# CircuitoPedaleiraTcc2.net
KiCad netlist of a schematic drawn in EAGLE
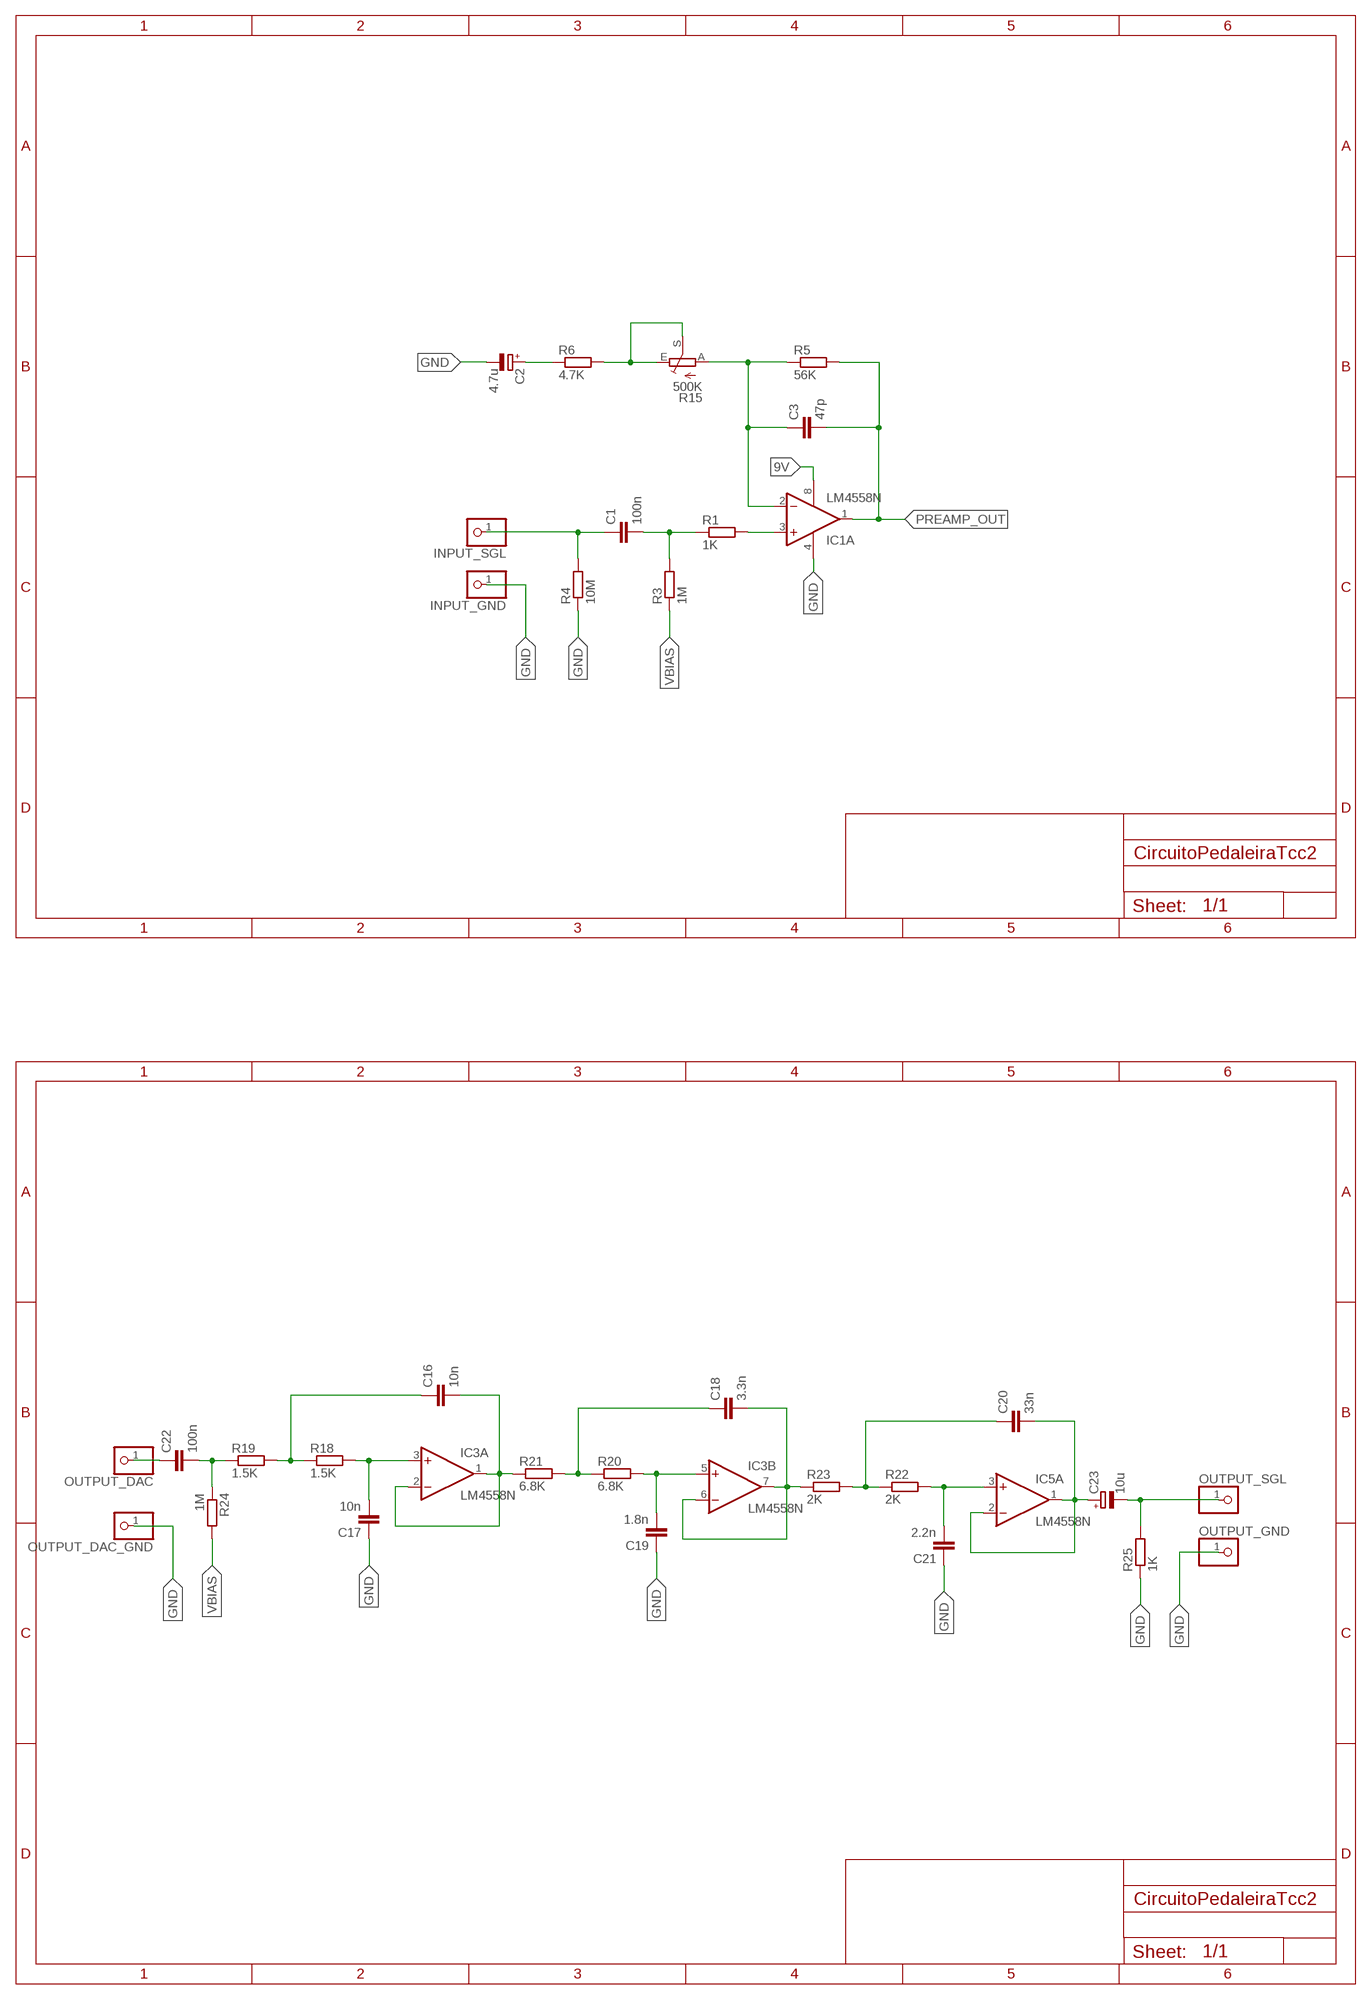
[diagram p0: schematic, sheet 1, part 1 of 3]
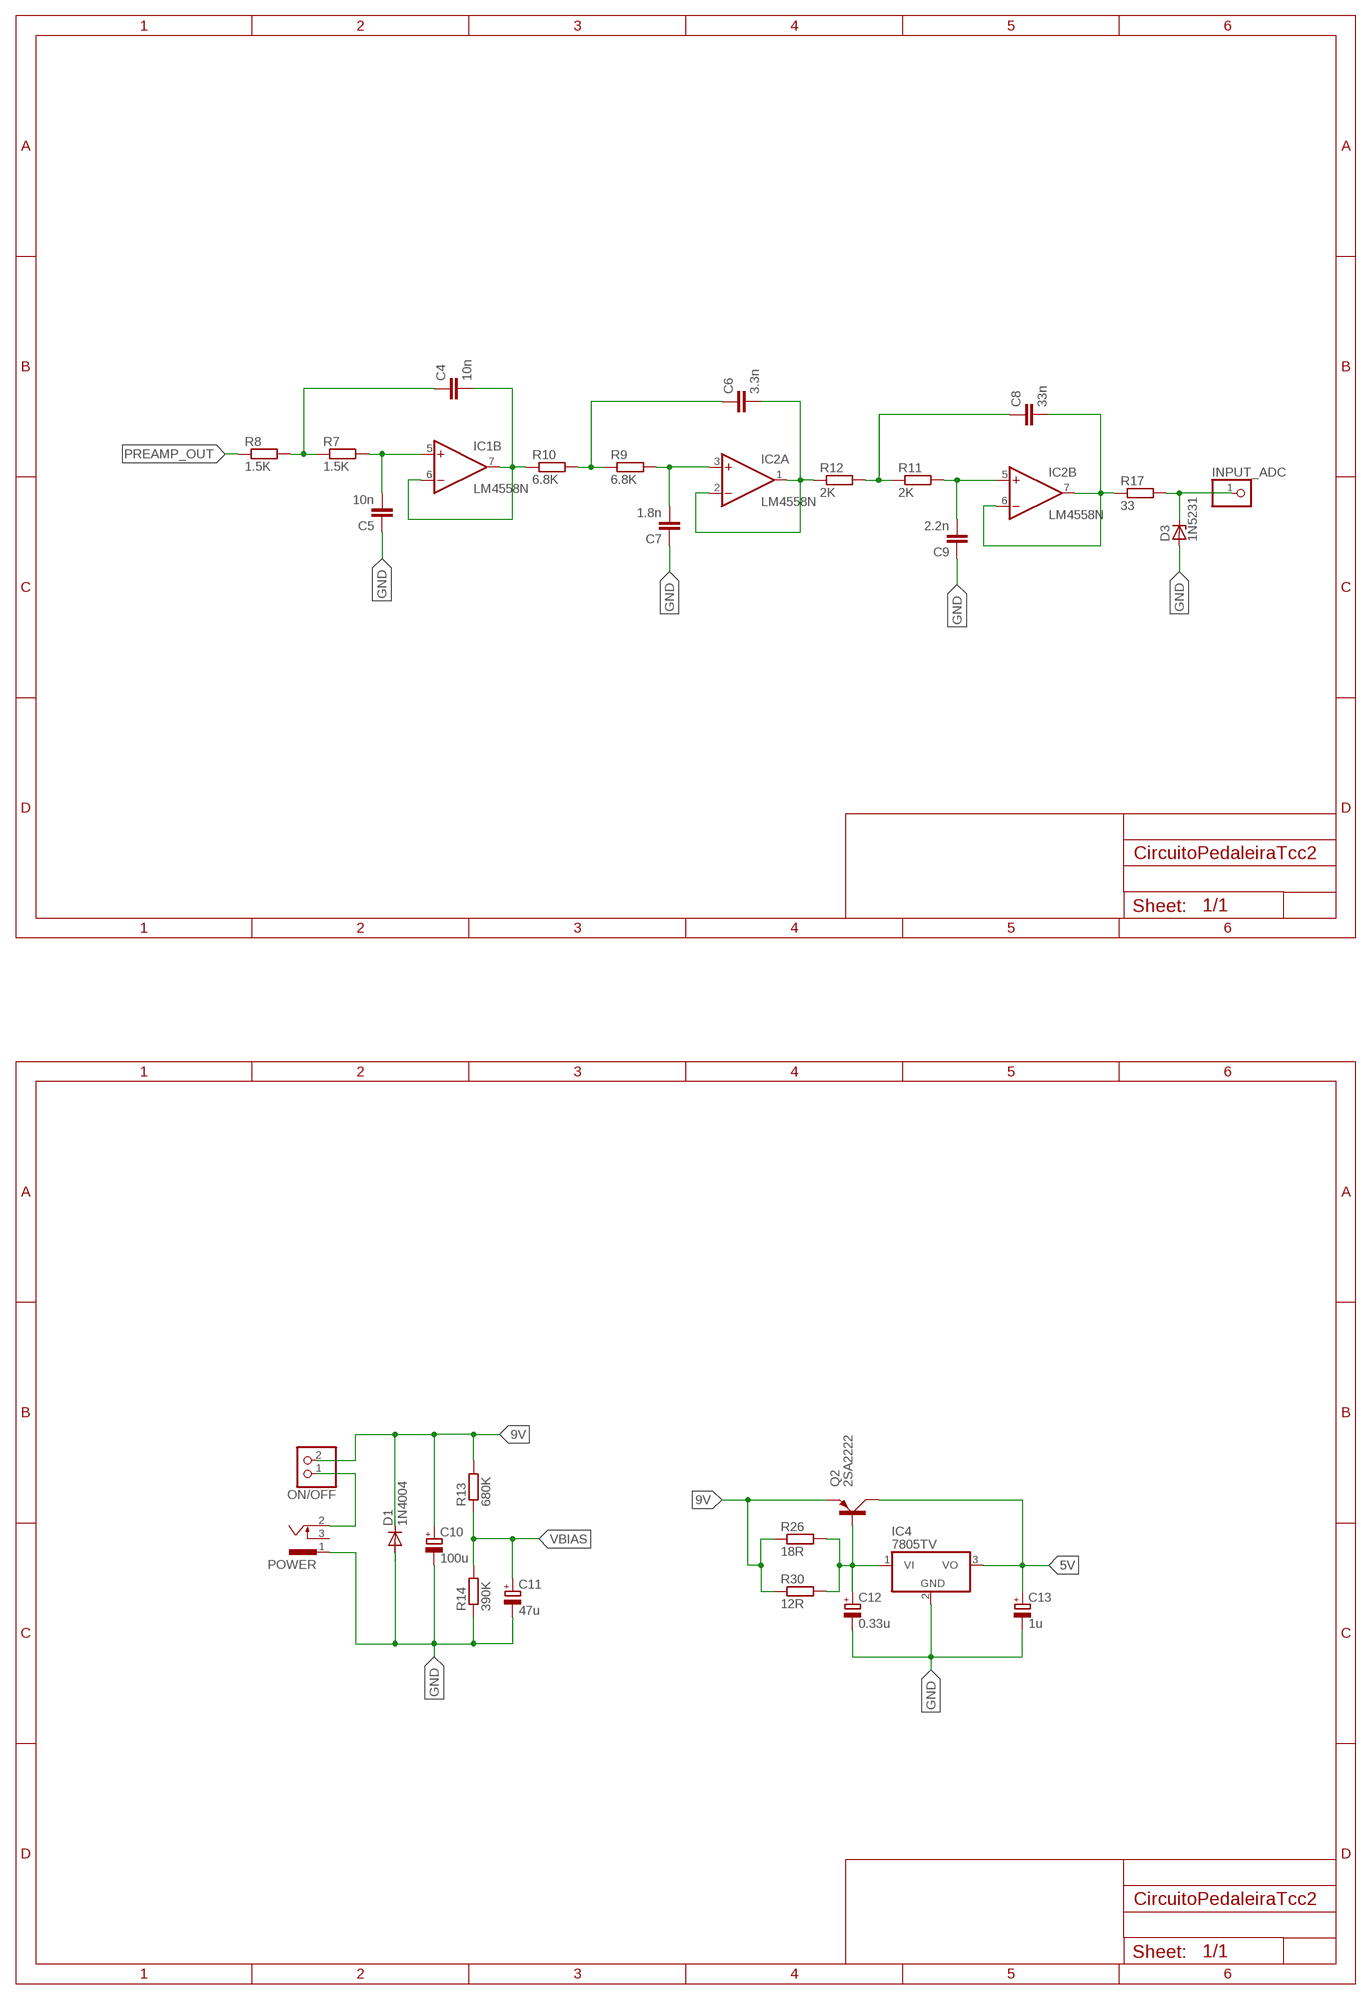
[diagram p1: schematic, sheet 1, part 2 of 3]
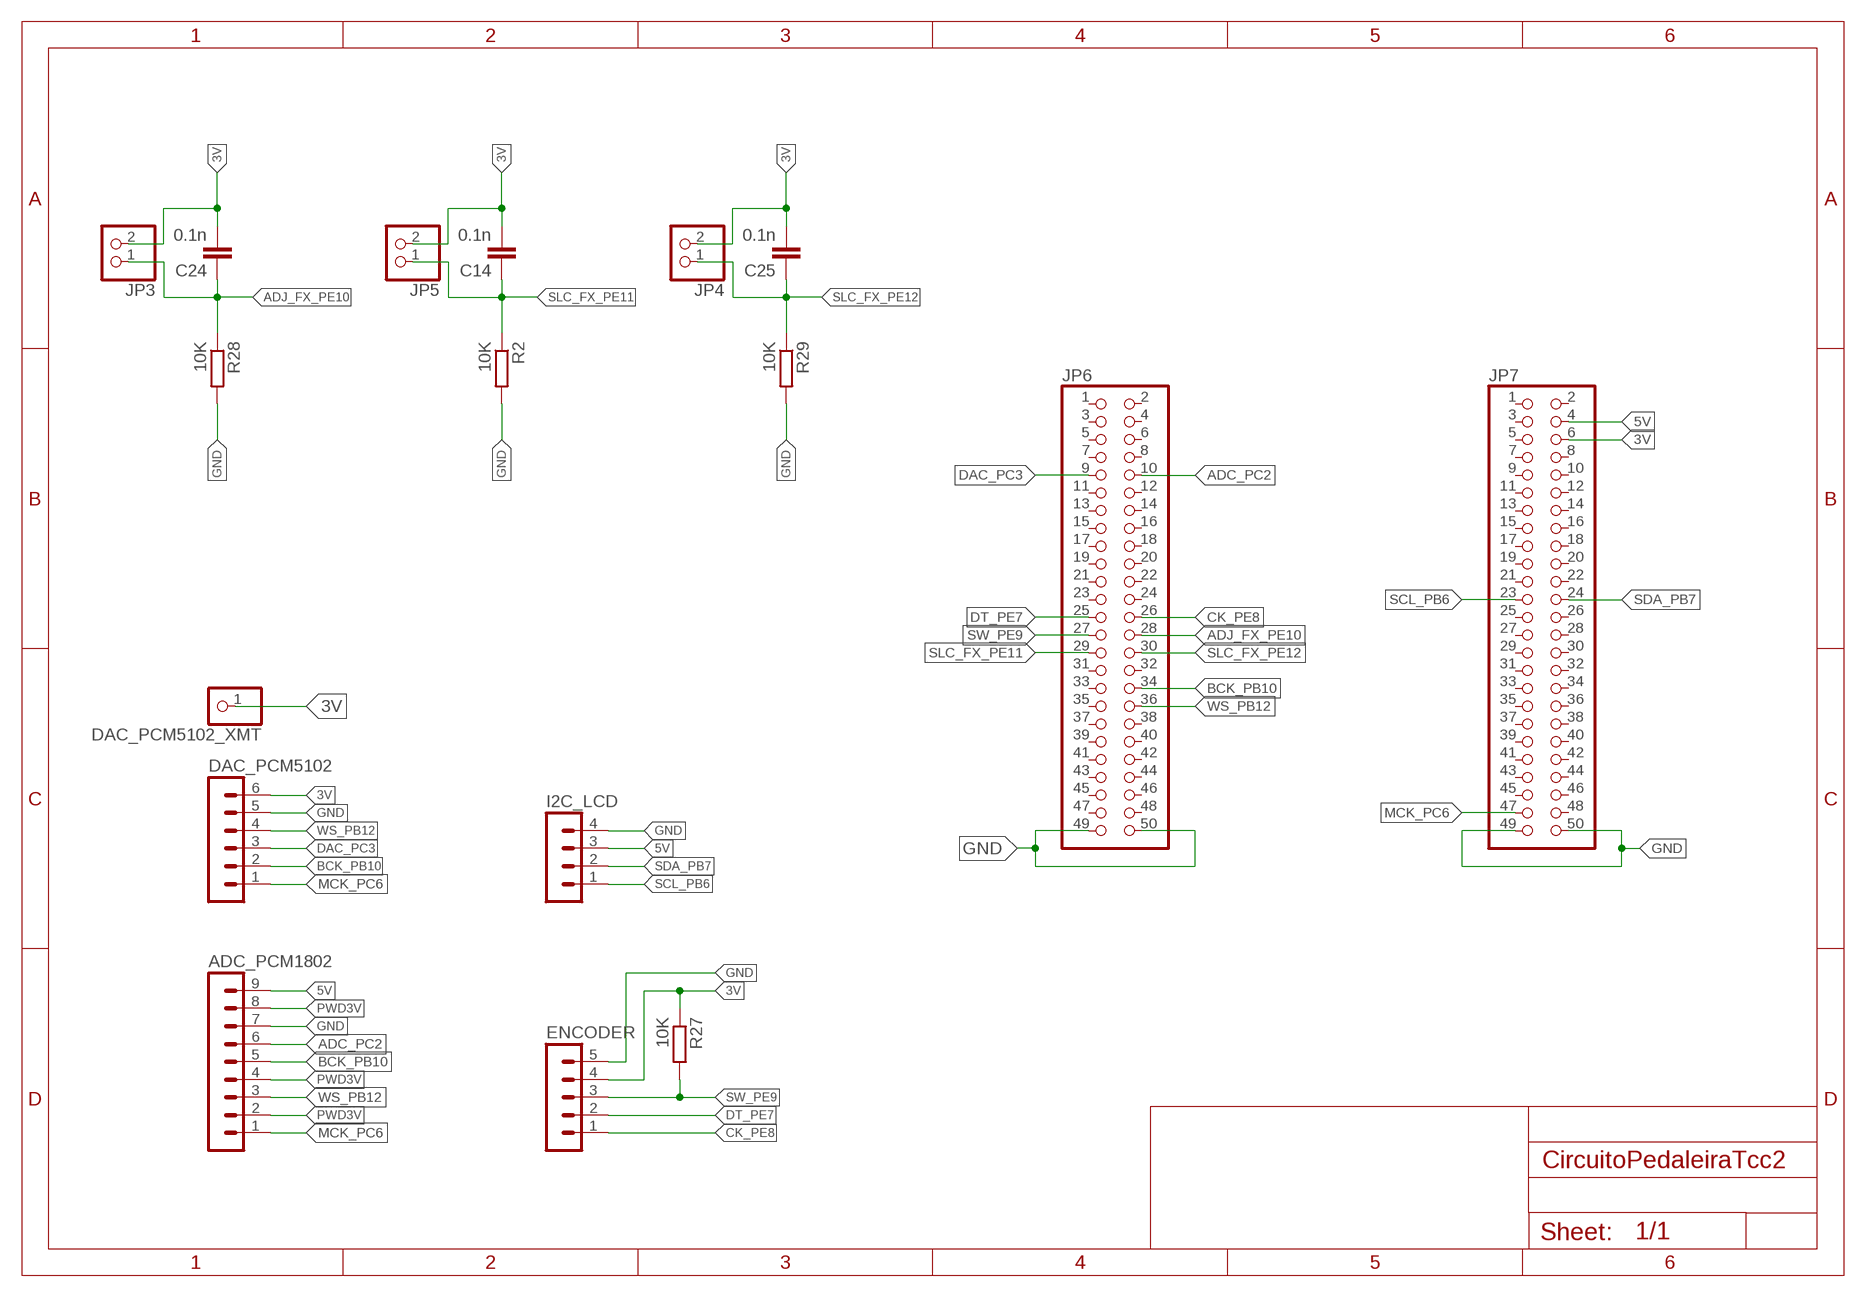
[diagram p2: schematic, sheet 1, part 3 of 3]

(export (version "E")
  (design (tool "Eeschema 10.0.6"))
  (components
    (comp (ref "ADC_PCM1802")
      (value "MA09-1")
      (footprint "eagle-import:MA09-1")
      (libsource (lib "eagle-import") (part "MA09-1"))
    )
    (comp (ref "C1")
      (value "100n")
      (footprint "eagle-import:C025-025X050")
      (libsource (lib "eagle-import") (part "C-EU025-025X050"))
    )
    (comp (ref "C2")
      (value "4.7u")
      (footprint "eagle-import:E2,5-6")
      (libsource (lib "eagle-import") (part "CPOL-EUE2.5-6"))
    )
    (comp (ref "C3")
      (value "47p")
      (footprint "eagle-import:C025-025X050")
      (libsource (lib "eagle-import") (part "C-EU025-025X050"))
    )
    (comp (ref "C4")
      (value "10n")
      (footprint "eagle-import:C025-025X050")
      (libsource (lib "eagle-import") (part "C-EU025-025X050"))
    )
    (comp (ref "C5")
      (value "10n")
      (footprint "eagle-import:C025-025X050")
      (libsource (lib "eagle-import") (part "C-EU025-025X050"))
    )
    (comp (ref "C6")
      (value "3.3n")
      (footprint "eagle-import:C025-025X050")
      (libsource (lib "eagle-import") (part "C-EU025-025X050"))
    )
    (comp (ref "C7")
      (value "1.8n")
      (footprint "eagle-import:C025-025X050")
      (libsource (lib "eagle-import") (part "C-EU025-025X050"))
    )
    (comp (ref "C8")
      (value "33n")
      (footprint "eagle-import:C025-025X050")
      (libsource (lib "eagle-import") (part "C-EU025-025X050"))
    )
    (comp (ref "C9")
      (value "2.2n")
      (footprint "eagle-import:C025-025X050")
      (libsource (lib "eagle-import") (part "C-EU025-025X050"))
    )
    (comp (ref "C10")
      (value "100u")
      (footprint "eagle-import:E2,5-6")
      (libsource (lib "eagle-import") (part "CPOL-EUE2.5-6"))
    )
    (comp (ref "C11")
      (value "47u")
      (footprint "eagle-import:E2,5-6")
      (libsource (lib "eagle-import") (part "CPOL-EUE2.5-6"))
    )
    (comp (ref "C12")
      (value "0.33u")
      (footprint "eagle-import:E2,5-6")
      (libsource (lib "eagle-import") (part "CPOL-EUE2.5-6"))
    )
    (comp (ref "C13")
      (value "1u")
      (footprint "eagle-import:E2,5-6")
      (libsource (lib "eagle-import") (part "CPOL-EUE2.5-6"))
    )
    (comp (ref "C14")
      (value "0.1n")
      (footprint "eagle-import:C025-025X050")
      (libsource (lib "eagle-import") (part "C-EU025-025X050"))
    )
    (comp (ref "C16")
      (value "10n")
      (footprint "eagle-import:C025-025X050")
      (libsource (lib "eagle-import") (part "C-EU025-025X050"))
    )
    (comp (ref "C17")
      (value "10n")
      (footprint "eagle-import:C025-025X050")
      (libsource (lib "eagle-import") (part "C-EU025-025X050"))
    )
    (comp (ref "C18")
      (value "3.3n")
      (footprint "eagle-import:C025-025X050")
      (libsource (lib "eagle-import") (part "C-EU025-025X050"))
    )
    (comp (ref "C19")
      (value "1.8n")
      (footprint "eagle-import:C025-025X050")
      (libsource (lib "eagle-import") (part "C-EU025-025X050"))
    )
    (comp (ref "C20")
      (value "33n")
      (footprint "eagle-import:C025-025X050")
      (libsource (lib "eagle-import") (part "C-EU025-025X050"))
    )
    (comp (ref "C21")
      (value "2.2n")
      (footprint "eagle-import:C025-025X050")
      (libsource (lib "eagle-import") (part "C-EU025-025X050"))
    )
    (comp (ref "C22")
      (value "100n")
      (footprint "eagle-import:C025-025X050")
      (libsource (lib "eagle-import") (part "C-EU025-025X050"))
    )
    (comp (ref "C23")
      (value "10u")
      (footprint "eagle-import:E2,5-6")
      (libsource (lib "eagle-import") (part "CPOL-EUE2.5-6"))
    )
    (comp (ref "C24")
      (value "0.1n")
      (footprint "eagle-import:C025-025X050")
      (libsource (lib "eagle-import") (part "C-EU025-025X050"))
    )
    (comp (ref "C25")
      (value "0.1n")
      (footprint "eagle-import:C025-025X050")
      (libsource (lib "eagle-import") (part "C-EU025-025X050"))
    )
    (comp (ref "D1")
      (value "1N4004")
      (footprint "eagle-import:DO41-10")
      (libsource (lib "eagle-import") (part "1N4004"))
    )
    (comp (ref "D3")
      (value "1N5231")
      (footprint "eagle-import:DO35Z10")
      (libsource (lib "eagle-import") (part "ZENER-DIODEDO35Z10"))
    )
    (comp (ref "DAC_PCM5102")
      (value "MA06-1")
      (footprint "eagle-import:MA06-1")
      (libsource (lib "eagle-import") (part "MA06-1"))
    )
    (comp (ref "DAC_PCM5102_XMT")
      (value "PINHD-1X1")
      (footprint "eagle-import:1X01")
      (libsource (lib "eagle-import") (part "PINHD-1X1"))
    )
    (comp (ref "ENCODER")
      (value "MA05-1")
      (footprint "eagle-import:MA05-1")
      (libsource (lib "eagle-import") (part "MA05-1"))
    )
    (comp (ref "I2C_LCD")
      (value "MA04-1")
      (footprint "eagle-import:MA04-1")
      (libsource (lib "eagle-import") (part "MA04-1"))
    )
    (comp (ref "IC1")
      (value "LM4558N")
      (footprint "eagle-import:DIL08")
      (libsource (lib "eagle-import") (part "4558NLM"))
    )
    (comp (ref "IC2")
      (value "LM4558N")
      (footprint "eagle-import:DIL08")
      (libsource (lib "eagle-import") (part "4558NLM"))
    )
    (comp (ref "IC3")
      (value "LM4558N")
      (footprint "eagle-import:DIL08")
      (libsource (lib "eagle-import") (part "4558NLM"))
    )
    (comp (ref "IC4")
      (value "7805TV")
      (footprint "eagle-import:TO220V")
      (libsource (lib "eagle-import") (part "78TV05"))
    )
    (comp (ref "IC5")
      (value "LM4558N")
      (footprint "eagle-import:DIL08")
      (libsource (lib "eagle-import") (part "4558NLM"))
    )
    (comp (ref "INPUT_ADC")
      (value "PINHD-1X1")
      (footprint "eagle-import:1X01")
      (libsource (lib "eagle-import") (part "PINHD-1X1"))
    )
    (comp (ref "INPUT_GND")
      (value "PINHD-1X1")
      (footprint "eagle-import:1X01")
      (libsource (lib "eagle-import") (part "PINHD-1X1"))
    )
    (comp (ref "INPUT_SGL")
      (value "PINHD-1X1")
      (footprint "eagle-import:1X01")
      (libsource (lib "eagle-import") (part "PINHD-1X1"))
    )
    (comp (ref "JP3")
      (value "PINHD-1X2")
      (footprint "eagle-import:1X02")
      (libsource (lib "eagle-import") (part "PINHD-1X2"))
    )
    (comp (ref "JP4")
      (value "PINHD-1X2")
      (footprint "eagle-import:1X02")
      (libsource (lib "eagle-import") (part "PINHD-1X2"))
    )
    (comp (ref "JP5")
      (value "PINHD-1X2")
      (footprint "eagle-import:1X02")
      (libsource (lib "eagle-import") (part "PINHD-1X2"))
    )
    (comp (ref "JP6")
      (value "PINHD-2X25")
      (footprint "eagle-import:2X25")
      (libsource (lib "eagle-import") (part "PINHD-2X25"))
    )
    (comp (ref "JP7")
      (value "PINHD-2X25")
      (footprint "eagle-import:2X25")
      (libsource (lib "eagle-import") (part "PINHD-2X25"))
    )
    (comp (ref "ON/OFF")
      (value "PINHD-1X2")
      (footprint "eagle-import:1X02")
      (libsource (lib "eagle-import") (part "PINHD-1X2"))
    )
    (comp (ref "OUTPUT_DAC")
      (value "PINHD-1X1")
      (footprint "eagle-import:1X01")
      (libsource (lib "eagle-import") (part "PINHD-1X1"))
    )
    (comp (ref "OUTPUT_DAC_GND")
      (value "PINHD-1X1")
      (footprint "eagle-import:1X01")
      (libsource (lib "eagle-import") (part "PINHD-1X1"))
    )
    (comp (ref "OUTPUT_GND")
      (value "PINHD-1X1")
      (footprint "eagle-import:1X01")
      (libsource (lib "eagle-import") (part "PINHD-1X1"))
    )
    (comp (ref "OUTPUT_SGL")
      (value "PINHD-1X1")
      (footprint "eagle-import:1X01")
      (libsource (lib "eagle-import") (part "PINHD-1X1"))
    )
    (comp (ref "POWER")
      (value "SCD-014A")
      (footprint "eagle-import:SCD-014-A")
      (libsource (lib "eagle-import") (part "SCD-014A"))
    )
    (comp (ref "Q2")
      (value "2SA2222")
      (footprint "eagle-import:TO220AV")
      (libsource (lib "eagle-import") (part "TIP42C"))
    )
    (comp (ref "R1")
      (value "1K")
      (footprint "eagle-import:0204_7")
      (libsource (lib "eagle-import") (part "R-EU_0204/7"))
    )
    (comp (ref "R2")
      (value "10K")
      (footprint "eagle-import:0204_7")
      (libsource (lib "eagle-import") (part "R-EU_0204/7"))
    )
    (comp (ref "R3")
      (value "1M")
      (footprint "eagle-import:0204_7")
      (libsource (lib "eagle-import") (part "R-EU_0204/7"))
    )
    (comp (ref "R4")
      (value "10M")
      (footprint "eagle-import:0204_7")
      (libsource (lib "eagle-import") (part "R-EU_0204/7"))
    )
    (comp (ref "R5")
      (value "56K")
      (footprint "eagle-import:0204_7")
      (libsource (lib "eagle-import") (part "R-EU_0204/7"))
    )
    (comp (ref "R6")
      (value "4.7K")
      (footprint "eagle-import:0204_7")
      (libsource (lib "eagle-import") (part "R-EU_0204/7"))
    )
    (comp (ref "R7")
      (value "1.5K")
      (footprint "eagle-import:0204_7")
      (libsource (lib "eagle-import") (part "R-EU_0204/7"))
    )
    (comp (ref "R8")
      (value "1.5K")
      (footprint "eagle-import:0204_7")
      (libsource (lib "eagle-import") (part "R-EU_0204/7"))
    )
    (comp (ref "R9")
      (value "6.8K")
      (footprint "eagle-import:0204_7")
      (libsource (lib "eagle-import") (part "R-EU_0204/7"))
    )
    (comp (ref "R10")
      (value "6.8K")
      (footprint "eagle-import:0204_7")
      (libsource (lib "eagle-import") (part "R-EU_0204/7"))
    )
    (comp (ref "R11")
      (value "2K")
      (footprint "eagle-import:0204_7")
      (libsource (lib "eagle-import") (part "R-EU_0204/7"))
    )
    (comp (ref "R12")
      (value "2K")
      (footprint "eagle-import:0204_7")
      (libsource (lib "eagle-import") (part "R-EU_0204/7"))
    )
    (comp (ref "R13")
      (value "680K")
      (footprint "eagle-import:0204_7")
      (libsource (lib "eagle-import") (part "R-EU_0204/7"))
    )
    (comp (ref "R14")
      (value "390K")
      (footprint "eagle-import:0204_7")
      (libsource (lib "eagle-import") (part "R-EU_0204/7"))
    )
    (comp (ref "R15")
      (value "500K")
      (footprint "eagle-import:B25X")
      (libsource (lib "eagle-import") (part "TRIM_EU-B25X"))
    )
    (comp (ref "R17")
      (value "33")
      (footprint "eagle-import:0204_7")
      (libsource (lib "eagle-import") (part "R-EU_0204/7"))
    )
    (comp (ref "R18")
      (value "1.5K")
      (footprint "eagle-import:0204_7")
      (libsource (lib "eagle-import") (part "R-EU_0204/7"))
    )
    (comp (ref "R19")
      (value "1.5K")
      (footprint "eagle-import:0204_7")
      (libsource (lib "eagle-import") (part "R-EU_0204/7"))
    )
    (comp (ref "R20")
      (value "6.8K")
      (footprint "eagle-import:0204_7")
      (libsource (lib "eagle-import") (part "R-EU_0204/7"))
    )
    (comp (ref "R21")
      (value "6.8K")
      (footprint "eagle-import:0204_7")
      (libsource (lib "eagle-import") (part "R-EU_0204/7"))
    )
    (comp (ref "R22")
      (value "2K")
      (footprint "eagle-import:0204_7")
      (libsource (lib "eagle-import") (part "R-EU_0204/7"))
    )
    (comp (ref "R23")
      (value "2K")
      (footprint "eagle-import:0204_7")
      (libsource (lib "eagle-import") (part "R-EU_0204/7"))
    )
    (comp (ref "R24")
      (value "1M")
      (footprint "eagle-import:0204_7")
      (libsource (lib "eagle-import") (part "R-EU_0204/7"))
    )
    (comp (ref "R25")
      (value "1K")
      (footprint "eagle-import:0204_7")
      (libsource (lib "eagle-import") (part "R-EU_0204/7"))
    )
    (comp (ref "R26")
      (value "18R")
      (footprint "eagle-import:0411_15")
      (libsource (lib "eagle-import") (part "R-EU_0411/15"))
    )
    (comp (ref "R27")
      (value "10K")
      (footprint "eagle-import:0204_7")
      (libsource (lib "eagle-import") (part "R-EU_0204/7"))
    )
    (comp (ref "R28")
      (value "10K")
      (footprint "eagle-import:0204_7")
      (libsource (lib "eagle-import") (part "R-EU_0204/7"))
    )
    (comp (ref "R29")
      (value "10K")
      (footprint "eagle-import:0204_7")
      (libsource (lib "eagle-import") (part "R-EU_0204/7"))
    )
    (comp (ref "R30")
      (value "12R")
      (footprint "eagle-import:0411_15")
      (libsource (lib "eagle-import") (part "R-EU_0411/15"))
    )
  )
  (nets
    (net (code "1") (name "3V") (class "Default")
      (node (ref "C14") (pin "2") (pinfunction "2_2") (pintype "passive"))
      (node (ref "C24") (pin "2") (pinfunction "2_2") (pintype "passive"))
      (node (ref "C25") (pin "2") (pinfunction "2_2") (pintype "passive"))
      (node (ref "DAC_PCM5102") (pin "6") (pinfunction "6_6") (pintype "passive"))
      (node (ref "DAC_PCM5102_XMT") (pin "1") (pinfunction "1_1") (pintype "passive"))
      (node (ref "ENCODER") (pin "4") (pinfunction "4_4") (pintype "passive"))
      (node (ref "JP3") (pin "2") (pinfunction "2_2") (pintype "passive"))
      (node (ref "JP4") (pin "2") (pinfunction "2_2") (pintype "passive"))
      (node (ref "JP5") (pin "2") (pinfunction "2_2") (pintype "passive"))
      (node (ref "JP7") (pin "6") (pinfunction "6_6") (pintype "passive"))
      (node (ref "R27") (pin "1") (pinfunction "1_1") (pintype "passive"))
    )
    (net (code "2") (name "5V") (class "Default")
      (node (ref "ADC_PCM1802") (pin "9") (pinfunction "9_9") (pintype "passive"))
      (node (ref "C13") (pin "+") (pinfunction "+_+") (pintype "passive"))
      (node (ref "I2C_LCD") (pin "3") (pinfunction "3_3") (pintype "passive"))
      (node (ref "IC4") (pin "3") (pinfunction "VO_3") (pintype "passive"))
      (node (ref "JP7") (pin "4") (pinfunction "4_4") (pintype "passive"))
      (node (ref "Q2") (pin "C") (pinfunction "C_C") (pintype "passive"))
    )
    (net (code "3") (name "9V") (class "Default")
      (node (ref "C10") (pin "+") (pinfunction "+_+") (pintype "passive"))
      (node (ref "D1") (pin "C") (pinfunction "C_C") (pintype "passive"))
      (node (ref "IC1") (pin "8") (pinfunction "V+_8") (pintype "power_in"))
      (node (ref "ON/OFF") (pin "2") (pinfunction "2_2") (pintype "passive"))
      (node (ref "Q2") (pin "E") (pinfunction "E_E") (pintype "passive"))
      (node (ref "R13") (pin "2") (pinfunction "2_2") (pintype "passive"))
      (node (ref "R26") (pin "1") (pinfunction "1_1") (pintype "passive"))
      (node (ref "R30") (pin "1") (pinfunction "1_1") (pintype "passive"))
    )
    (net (code "4") (name "ADC_PC2") (class "Default")
      (node (ref "ADC_PCM1802") (pin "6") (pinfunction "6_6") (pintype "passive"))
      (node (ref "JP6") (pin "10") (pinfunction "10_10") (pintype "passive"))
    )
    (net (code "5") (name "ADJ_FX_PE10") (class "Default")
      (node (ref "C24") (pin "1") (pinfunction "1_1") (pintype "passive"))
      (node (ref "JP3") (pin "1") (pinfunction "1_1") (pintype "passive"))
      (node (ref "JP6") (pin "28") (pinfunction "28_28") (pintype "passive"))
      (node (ref "R28") (pin "1") (pinfunction "1_1") (pintype "passive"))
    )
    (net (code "6") (name "BCK_PB10") (class "Default")
      (node (ref "ADC_PCM1802") (pin "5") (pinfunction "5_5") (pintype "passive"))
      (node (ref "DAC_PCM5102") (pin "2") (pinfunction "2_2") (pintype "passive"))
      (node (ref "JP6") (pin "34") (pinfunction "34_34") (pintype "passive"))
    )
    (net (code "7") (name "CK_PE8") (class "Default")
      (node (ref "ENCODER") (pin "1") (pinfunction "1_1") (pintype "passive"))
      (node (ref "JP6") (pin "26") (pinfunction "26_26") (pintype "passive"))
    )
    (net (code "8") (name "DAC_PC3") (class "Default")
      (node (ref "DAC_PCM5102") (pin "3") (pinfunction "3_3") (pintype "passive"))
      (node (ref "JP6") (pin "9") (pinfunction "9_9") (pintype "passive"))
    )
    (net (code "9") (name "DT_PE7") (class "Default")
      (node (ref "ENCODER") (pin "2") (pinfunction "2_2") (pintype "passive"))
      (node (ref "JP6") (pin "25") (pinfunction "25_25") (pintype "passive"))
    )
    (net (code "10") (name "GND") (class "Default")
      (node (ref "ADC_PCM1802") (pin "7") (pinfunction "7_7") (pintype "passive"))
      (node (ref "C10") (pin "-") (pinfunction "-_-") (pintype "passive"))
      (node (ref "C11") (pin "-") (pinfunction "-_-") (pintype "passive"))
      (node (ref "C12") (pin "-") (pinfunction "-_-") (pintype "passive"))
      (node (ref "C13") (pin "-") (pinfunction "-_-") (pintype "passive"))
      (node (ref "C17") (pin "1") (pinfunction "1_1") (pintype "passive"))
      (node (ref "C19") (pin "1") (pinfunction "1_1") (pintype "passive"))
      (node (ref "C2") (pin "-") (pinfunction "-_-") (pintype "passive"))
      (node (ref "C21") (pin "1") (pinfunction "1_1") (pintype "passive"))
      (node (ref "C5") (pin "1") (pinfunction "1_1") (pintype "passive"))
      (node (ref "C7") (pin "1") (pinfunction "1_1") (pintype "passive"))
      (node (ref "C9") (pin "1") (pinfunction "1_1") (pintype "passive"))
      (node (ref "D1") (pin "A") (pinfunction "A_A") (pintype "passive"))
      (node (ref "D3") (pin "A") (pinfunction "A_A") (pintype "passive"))
      (node (ref "DAC_PCM5102") (pin "5") (pinfunction "5_5") (pintype "passive"))
      (node (ref "ENCODER") (pin "5") (pinfunction "5_5") (pintype "passive"))
      (node (ref "I2C_LCD") (pin "4") (pinfunction "4_4") (pintype "passive"))
      (node (ref "IC1") (pin "4") (pinfunction "V-_4") (pintype "power_in"))
      (node (ref "IC4") (pin "2") (pinfunction "GND_2") (pintype "passive"))
      (node (ref "INPUT_GND") (pin "1") (pinfunction "1_1") (pintype "passive"))
      (node (ref "JP6") (pin "49") (pinfunction "49_49") (pintype "passive"))
      (node (ref "JP6") (pin "50") (pinfunction "50_50") (pintype "passive"))
      (node (ref "JP7") (pin "49") (pinfunction "49_49") (pintype "passive"))
      (node (ref "JP7") (pin "50") (pinfunction "50_50") (pintype "passive"))
      (node (ref "OUTPUT_DAC_GND") (pin "1") (pinfunction "1_1") (pintype "passive"))
      (node (ref "OUTPUT_GND") (pin "1") (pinfunction "1_1") (pintype "passive"))
      (node (ref "POWER") (pin "1") (pinfunction "1_1") (pintype "passive"))
      (node (ref "R14") (pin "1") (pinfunction "1_1") (pintype "passive"))
      (node (ref "R2") (pin "2") (pinfunction "2_2") (pintype "passive"))
      (node (ref "R25") (pin "1") (pinfunction "1_1") (pintype "passive"))
      (node (ref "R28") (pin "2") (pinfunction "2_2") (pintype "passive"))
      (node (ref "R29") (pin "2") (pinfunction "2_2") (pintype "passive"))
      (node (ref "R4") (pin "1") (pinfunction "1_1") (pintype "passive"))
    )
    (net (code "11") (name "MCK_PC6") (class "Default")
      (node (ref "ADC_PCM1802") (pin "1") (pinfunction "1_1") (pintype "passive"))
      (node (ref "DAC_PCM5102") (pin "1") (pinfunction "1_1") (pintype "passive"))
      (node (ref "JP7") (pin "47") (pinfunction "47_47") (pintype "passive"))
    )
    (net (code "12") (name "Net-(C1-Pad1)") (class "Default")
      (node (ref "C1") (pin "1") (pinfunction "1_1") (pintype "passive"))
      (node (ref "INPUT_SGL") (pin "1") (pinfunction "1_1") (pintype "passive"))
      (node (ref "R4") (pin "2") (pinfunction "2_2") (pintype "passive"))
    )
    (net (code "13") (name "Net-(C1-Pad2)") (class "Default")
      (node (ref "C1") (pin "2") (pinfunction "2_2") (pintype "passive"))
      (node (ref "R1") (pin "1") (pinfunction "1_1") (pintype "passive"))
      (node (ref "R3") (pin "2") (pinfunction "2_2") (pintype "passive"))
    )
    (net (code "14") (name "Net-(C2-Pad+)") (class "Default")
      (node (ref "C2") (pin "+") (pinfunction "+_+") (pintype "passive"))
      (node (ref "R6") (pin "1") (pinfunction "1_1") (pintype "passive"))
    )
    (net (code "15") (name "Net-(C4-Pad1)") (class "Default")
      (node (ref "C4") (pin "1") (pinfunction "1_1") (pintype "passive"))
      (node (ref "R7") (pin "1") (pinfunction "1_1") (pintype "passive"))
      (node (ref "R8") (pin "2") (pinfunction "2_2") (pintype "passive"))
    )
    (net (code "16") (name "Net-(C6-Pad1)") (class "Default")
      (node (ref "C6") (pin "1") (pinfunction "1_1") (pintype "passive"))
      (node (ref "R10") (pin "2") (pinfunction "2_2") (pintype "passive"))
      (node (ref "R9") (pin "1") (pinfunction "1_1") (pintype "passive"))
    )
    (net (code "17") (name "Net-(C8-Pad1)") (class "Default")
      (node (ref "C8") (pin "1") (pinfunction "1_1") (pintype "passive"))
      (node (ref "R11") (pin "1") (pinfunction "1_1") (pintype "passive"))
      (node (ref "R12") (pin "2") (pinfunction "2_2") (pintype "passive"))
    )
    (net (code "18") (name "Net-(C16-Pad1)") (class "Default")
      (node (ref "C16") (pin "1") (pinfunction "1_1") (pintype "passive"))
      (node (ref "R18") (pin "1") (pinfunction "1_1") (pintype "passive"))
      (node (ref "R19") (pin "2") (pinfunction "2_2") (pintype "passive"))
    )
    (net (code "19") (name "Net-(C18-Pad1)") (class "Default")
      (node (ref "C18") (pin "1") (pinfunction "1_1") (pintype "passive"))
      (node (ref "R20") (pin "1") (pinfunction "1_1") (pintype "passive"))
      (node (ref "R21") (pin "2") (pinfunction "2_2") (pintype "passive"))
    )
    (net (code "20") (name "Net-(C20-Pad1)") (class "Default")
      (node (ref "C20") (pin "1") (pinfunction "1_1") (pintype "passive"))
      (node (ref "R22") (pin "1") (pinfunction "1_1") (pintype "passive"))
      (node (ref "R23") (pin "2") (pinfunction "2_2") (pintype "passive"))
    )
    (net (code "21") (name "Net-(C22-Pad1)") (class "Default")
      (node (ref "C22") (pin "1") (pinfunction "1_1") (pintype "passive"))
      (node (ref "OUTPUT_DAC") (pin "1") (pinfunction "1_1") (pintype "passive"))
    )
    (net (code "22") (name "Net-(C22-Pad2)") (class "Default")
      (node (ref "C22") (pin "2") (pinfunction "2_2") (pintype "passive"))
      (node (ref "R19") (pin "1") (pinfunction "1_1") (pintype "passive"))
      (node (ref "R24") (pin "1") (pinfunction "1_1") (pintype "passive"))
    )
    (net (code "23") (name "Net-(C23-Pad-)") (class "Default")
      (node (ref "C23") (pin "-") (pinfunction "-_-") (pintype "passive"))
      (node (ref "OUTPUT_SGL") (pin "1") (pinfunction "1_1") (pintype "passive"))
      (node (ref "R25") (pin "2") (pinfunction "2_2") (pintype "passive"))
    )
    (net (code "24") (name "Net-(D3-PadC)") (class "Default")
      (node (ref "D3") (pin "C") (pinfunction "C_C") (pintype "passive"))
      (node (ref "INPUT_ADC") (pin "1") (pinfunction "1_1") (pintype "passive"))
      (node (ref "R17") (pin "2") (pinfunction "2_2") (pintype "passive"))
    )
    (net (code "25") (name "Net-(IC1A-+IN)") (class "Default")
      (node (ref "IC1") (pin "3") (pinfunction "+IN_3") (pintype "input"))
      (node (ref "R1") (pin "2") (pinfunction "2_2") (pintype "passive"))
    )
    (net (code "26") (name "Net-(IC1A--IN)") (class "Default")
      (node (ref "C3") (pin "1") (pinfunction "1_1") (pintype "passive"))
      (node (ref "IC1") (pin "2") (pinfunction "-IN_2") (pintype "input"))
      (node (ref "R15") (pin "A") (pinfunction "A_A") (pintype "passive"))
      (node (ref "R5") (pin "1") (pinfunction "1_1") (pintype "passive"))
    )
    (net (code "27") (name "Net-(IC1B-+IN)") (class "Default")
      (node (ref "C5") (pin "2") (pinfunction "2_2") (pintype "passive"))
      (node (ref "IC1") (pin "5") (pinfunction "+IN_5") (pintype "input"))
      (node (ref "R7") (pin "2") (pinfunction "2_2") (pintype "passive"))
    )
    (net (code "28") (name "Net-(IC1B--IN)") (class "Default")
      (node (ref "C4") (pin "2") (pinfunction "2_2") (pintype "passive"))
      (node (ref "IC1") (pin "6") (pinfunction "-IN_6") (pintype "input"))
      (node (ref "IC1") (pin "7") (pinfunction "OUT_7") (pintype "output"))
      (node (ref "R10") (pin "1") (pinfunction "1_1") (pintype "passive"))
    )
    (net (code "29") (name "Net-(IC2A-+IN)") (class "Default")
      (node (ref "C7") (pin "2") (pinfunction "2_2") (pintype "passive"))
      (node (ref "IC2") (pin "3") (pinfunction "+IN_3") (pintype "input"))
      (node (ref "R9") (pin "2") (pinfunction "2_2") (pintype "passive"))
    )
    (net (code "30") (name "Net-(IC2A--IN)") (class "Default")
      (node (ref "C6") (pin "2") (pinfunction "2_2") (pintype "passive"))
      (node (ref "IC2") (pin "1") (pinfunction "OUT_1") (pintype "output"))
      (node (ref "IC2") (pin "2") (pinfunction "-IN_2") (pintype "input"))
      (node (ref "R12") (pin "1") (pinfunction "1_1") (pintype "passive"))
    )
    (net (code "31") (name "Net-(IC2B-+IN)") (class "Default")
      (node (ref "C9") (pin "2") (pinfunction "2_2") (pintype "passive"))
      (node (ref "IC2") (pin "5") (pinfunction "+IN_5") (pintype "input"))
      (node (ref "R11") (pin "2") (pinfunction "2_2") (pintype "passive"))
    )
    (net (code "32") (name "Net-(IC2B--IN)") (class "Default")
      (node (ref "C8") (pin "2") (pinfunction "2_2") (pintype "passive"))
      (node (ref "IC2") (pin "6") (pinfunction "-IN_6") (pintype "input"))
      (node (ref "IC2") (pin "7") (pinfunction "OUT_7") (pintype "output"))
      (node (ref "R17") (pin "1") (pinfunction "1_1") (pintype "passive"))
    )
    (net (code "33") (name "Net-(IC3A-+IN)") (class "Default")
      (node (ref "C17") (pin "2") (pinfunction "2_2") (pintype "passive"))
      (node (ref "IC3") (pin "3") (pinfunction "+IN_3") (pintype "input"))
      (node (ref "R18") (pin "2") (pinfunction "2_2") (pintype "passive"))
    )
    (net (code "34") (name "Net-(IC3A--IN)") (class "Default")
      (node (ref "C16") (pin "2") (pinfunction "2_2") (pintype "passive"))
      (node (ref "IC3") (pin "1") (pinfunction "OUT_1") (pintype "output"))
      (node (ref "IC3") (pin "2") (pinfunction "-IN_2") (pintype "input"))
      (node (ref "R21") (pin "1") (pinfunction "1_1") (pintype "passive"))
    )
    (net (code "35") (name "Net-(IC3B-+IN)") (class "Default")
      (node (ref "C19") (pin "2") (pinfunction "2_2") (pintype "passive"))
      (node (ref "IC3") (pin "5") (pinfunction "+IN_5") (pintype "input"))
      (node (ref "R20") (pin "2") (pinfunction "2_2") (pintype "passive"))
    )
    (net (code "36") (name "Net-(IC3B--IN)") (class "Default")
      (node (ref "C18") (pin "2") (pinfunction "2_2") (pintype "passive"))
      (node (ref "IC3") (pin "6") (pinfunction "-IN_6") (pintype "input"))
      (node (ref "IC3") (pin "7") (pinfunction "OUT_7") (pintype "output"))
      (node (ref "R23") (pin "1") (pinfunction "1_1") (pintype "passive"))
    )
    (net (code "37") (name "Net-(IC4-VI)") (class "Default")
      (node (ref "C12") (pin "+") (pinfunction "+_+") (pintype "passive"))
      (node (ref "IC4") (pin "1") (pinfunction "VI_1") (pintype "input"))
      (node (ref "Q2") (pin "B") (pinfunction "B_B") (pintype "passive"))
      (node (ref "R26") (pin "2") (pinfunction "2_2") (pintype "passive"))
      (node (ref "R30") (pin "2") (pinfunction "2_2") (pintype "passive"))
    )
    (net (code "38") (name "Net-(IC5A-+IN)") (class "Default")
      (node (ref "C21") (pin "2") (pinfunction "2_2") (pintype "passive"))
      (node (ref "IC5") (pin "3") (pinfunction "+IN_3") (pintype "input"))
      (node (ref "R22") (pin "2") (pinfunction "2_2") (pintype "passive"))
    )
    (net (code "39") (name "Net-(IC5A--IN)") (class "Default")
      (node (ref "C20") (pin "2") (pinfunction "2_2") (pintype "passive"))
      (node (ref "C23") (pin "+") (pinfunction "+_+") (pintype "passive"))
      (node (ref "IC5") (pin "1") (pinfunction "OUT_1") (pintype "output"))
      (node (ref "IC5") (pin "2") (pinfunction "-IN_2") (pintype "input"))
    )
    (net (code "40") (name "Net-(ON/OFF-Pad1)") (class "Default")
      (node (ref "ON/OFF") (pin "1") (pinfunction "1_1") (pintype "passive"))
      (node (ref "POWER") (pin "2") (pinfunction "2_2") (pintype "passive"))
    )
    (net (code "41") (name "Net-(R15-PadE)") (class "Default")
      (node (ref "R15") (pin "E") (pinfunction "E_E") (pintype "passive"))
      (node (ref "R15") (pin "S") (pinfunction "S_S") (pintype "passive"))
      (node (ref "R6") (pin "2") (pinfunction "2_2") (pintype "passive"))
    )
    (net (code "42") (name "PREAMP_OUT") (class "Default")
      (node (ref "C3") (pin "2") (pinfunction "2_2") (pintype "passive"))
      (node (ref "IC1") (pin "1") (pinfunction "OUT_1") (pintype "output"))
      (node (ref "R5") (pin "2") (pinfunction "2_2") (pintype "passive"))
      (node (ref "R8") (pin "1") (pinfunction "1_1") (pintype "passive"))
    )
    (net (code "43") (name "PWD3V") (class "Default")
      (node (ref "ADC_PCM1802") (pin "2") (pinfunction "2_2") (pintype "passive"))
      (node (ref "ADC_PCM1802") (pin "4") (pinfunction "4_4") (pintype "passive"))
      (node (ref "ADC_PCM1802") (pin "8") (pinfunction "8_8") (pintype "passive"))
    )
    (net (code "44") (name "SCL_PB6") (class "Default")
      (node (ref "I2C_LCD") (pin "1") (pinfunction "1_1") (pintype "passive"))
      (node (ref "JP7") (pin "23") (pinfunction "23_23") (pintype "passive"))
    )
    (net (code "45") (name "SDA_PB7") (class "Default")
      (node (ref "I2C_LCD") (pin "2") (pinfunction "2_2") (pintype "passive"))
      (node (ref "JP7") (pin "24") (pinfunction "24_24") (pintype "passive"))
    )
    (net (code "46") (name "SLC_FX_PE11") (class "Default")
      (node (ref "C14") (pin "1") (pinfunction "1_1") (pintype "passive"))
      (node (ref "JP5") (pin "1") (pinfunction "1_1") (pintype "passive"))
      (node (ref "JP6") (pin "29") (pinfunction "29_29") (pintype "passive"))
      (node (ref "R2") (pin "1") (pinfunction "1_1") (pintype "passive"))
    )
    (net (code "47") (name "SLC_FX_PE12") (class "Default")
      (node (ref "C25") (pin "1") (pinfunction "1_1") (pintype "passive"))
      (node (ref "JP4") (pin "1") (pinfunction "1_1") (pintype "passive"))
      (node (ref "JP6") (pin "30") (pinfunction "30_30") (pintype "passive"))
      (node (ref "R29") (pin "1") (pinfunction "1_1") (pintype "passive"))
    )
    (net (code "48") (name "SW_PE9") (class "Default")
      (node (ref "ENCODER") (pin "3") (pinfunction "3_3") (pintype "passive"))
      (node (ref "JP6") (pin "27") (pinfunction "27_27") (pintype "passive"))
      (node (ref "R27") (pin "2") (pinfunction "2_2") (pintype "passive"))
    )
    (net (code "49") (name "VBIAS") (class "Default")
      (node (ref "C11") (pin "+") (pinfunction "+_+") (pintype "passive"))
      (node (ref "R13") (pin "1") (pinfunction "1_1") (pintype "passive"))
      (node (ref "R14") (pin "2") (pinfunction "2_2") (pintype "passive"))
      (node (ref "R24") (pin "2") (pinfunction "2_2") (pintype "passive"))
      (node (ref "R3") (pin "1") (pinfunction "1_1") (pintype "passive"))
    )
    (net (code "50") (name "WS_PB12") (class "Default")
      (node (ref "ADC_PCM1802") (pin "3") (pinfunction "3_3") (pintype "passive"))
      (node (ref "DAC_PCM5102") (pin "4") (pinfunction "4_4") (pintype "passive"))
      (node (ref "JP6") (pin "36") (pinfunction "36_36") (pintype "passive"))
    )
    (net (code "51") (name "unconnected-(JP6-Pad1)") (class "Default")
      (node (ref "JP6") (pin "1") (pinfunction "1_1") (pintype "passive"))
    )
    (net (code "52") (name "unconnected-(JP6-Pad2)") (class "Default")
      (node (ref "JP6") (pin "2") (pinfunction "2_2") (pintype "passive"))
    )
    (net (code "53") (name "unconnected-(JP6-Pad3)") (class "Default")
      (node (ref "JP6") (pin "3") (pinfunction "3_3") (pintype "passive"))
    )
    (net (code "54") (name "unconnected-(JP6-Pad4)") (class "Default")
      (node (ref "JP6") (pin "4") (pinfunction "4_4") (pintype "passive"))
    )
    (net (code "55") (name "unconnected-(JP6-Pad5)") (class "Default")
      (node (ref "JP6") (pin "5") (pinfunction "5_5") (pintype "passive"))
    )
    (net (code "56") (name "unconnected-(JP6-Pad6)") (class "Default")
      (node (ref "JP6") (pin "6") (pinfunction "6_6") (pintype "passive"))
    )
    (net (code "57") (name "unconnected-(JP6-Pad7)") (class "Default")
      (node (ref "JP6") (pin "7") (pinfunction "7_7") (pintype "passive"))
    )
    (net (code "58") (name "unconnected-(JP6-Pad8)") (class "Default")
      (node (ref "JP6") (pin "8") (pinfunction "8_8") (pintype "passive"))
    )
    (net (code "59") (name "unconnected-(JP6-Pad11)") (class "Default")
      (node (ref "JP6") (pin "11") (pinfunction "11_11") (pintype "passive"))
    )
    (net (code "60") (name "unconnected-(JP6-Pad12)") (class "Default")
      (node (ref "JP6") (pin "12") (pinfunction "12_12") (pintype "passive"))
    )
    (net (code "61") (name "unconnected-(JP6-Pad13)") (class "Default")
      (node (ref "JP6") (pin "13") (pinfunction "13_13") (pintype "passive"))
    )
    (net (code "62") (name "unconnected-(JP6-Pad14)") (class "Default")
      (node (ref "JP6") (pin "14") (pinfunction "14_14") (pintype "passive"))
    )
    (net (code "63") (name "unconnected-(JP6-Pad15)") (class "Default")
      (node (ref "JP6") (pin "15") (pinfunction "15_15") (pintype "passive"))
    )
    (net (code "64") (name "unconnected-(JP6-Pad16)") (class "Default")
      (node (ref "JP6") (pin "16") (pinfunction "16_16") (pintype "passive"))
    )
    (net (code "65") (name "unconnected-(JP6-Pad17)") (class "Default")
      (node (ref "JP6") (pin "17") (pinfunction "17_17") (pintype "passive"))
    )
    (net (code "66") (name "unconnected-(JP6-Pad18)") (class "Default")
      (node (ref "JP6") (pin "18") (pinfunction "18_18") (pintype "passive"))
    )
    (net (code "67") (name "unconnected-(JP6-Pad19)") (class "Default")
      (node (ref "JP6") (pin "19") (pinfunction "19_19") (pintype "passive"))
    )
    (net (code "68") (name "unconnected-(JP6-Pad20)") (class "Default")
      (node (ref "JP6") (pin "20") (pinfunction "20_20") (pintype "passive"))
    )
    (net (code "69") (name "unconnected-(JP6-Pad21)") (class "Default")
      (node (ref "JP6") (pin "21") (pinfunction "21_21") (pintype "passive"))
    )
    (net (code "70") (name "unconnected-(JP6-Pad22)") (class "Default")
      (node (ref "JP6") (pin "22") (pinfunction "22_22") (pintype "passive"))
    )
    (net (code "71") (name "unconnected-(JP6-Pad23)") (class "Default")
      (node (ref "JP6") (pin "23") (pinfunction "23_23") (pintype "passive"))
    )
    (net (code "72") (name "unconnected-(JP6-Pad24)") (class "Default")
      (node (ref "JP6") (pin "24") (pinfunction "24_24") (pintype "passive"))
    )
    (net (code "73") (name "unconnected-(JP6-Pad31)") (class "Default")
      (node (ref "JP6") (pin "31") (pinfunction "31_31") (pintype "passive"))
    )
    (net (code "74") (name "unconnected-(JP6-Pad32)") (class "Default")
      (node (ref "JP6") (pin "32") (pinfunction "32_32") (pintype "passive"))
    )
    (net (code "75") (name "unconnected-(JP6-Pad33)") (class "Default")
      (node (ref "JP6") (pin "33") (pinfunction "33_33") (pintype "passive"))
    )
    (net (code "76") (name "unconnected-(JP6-Pad35)") (class "Default")
      (node (ref "JP6") (pin "35") (pinfunction "35_35") (pintype "passive"))
    )
    (net (code "77") (name "unconnected-(JP6-Pad37)") (class "Default")
      (node (ref "JP6") (pin "37") (pinfunction "37_37") (pintype "passive"))
    )
    (net (code "78") (name "unconnected-(JP6-Pad38)") (class "Default")
      (node (ref "JP6") (pin "38") (pinfunction "38_38") (pintype "passive"))
    )
    (net (code "79") (name "unconnected-(JP6-Pad39)") (class "Default")
      (node (ref "JP6") (pin "39") (pinfunction "39_39") (pintype "passive"))
    )
    (net (code "80") (name "unconnected-(JP6-Pad40)") (class "Default")
      (node (ref "JP6") (pin "40") (pinfunction "40_40") (pintype "passive"))
    )
    (net (code "81") (name "unconnected-(JP6-Pad41)") (class "Default")
      (node (ref "JP6") (pin "41") (pinfunction "41_41") (pintype "passive"))
    )
    (net (code "82") (name "unconnected-(JP6-Pad42)") (class "Default")
      (node (ref "JP6") (pin "42") (pinfunction "42_42") (pintype "passive"))
    )
    (net (code "83") (name "unconnected-(JP6-Pad43)") (class "Default")
      (node (ref "JP6") (pin "43") (pinfunction "43_43") (pintype "passive"))
    )
    (net (code "84") (name "unconnected-(JP6-Pad44)") (class "Default")
      (node (ref "JP6") (pin "44") (pinfunction "44_44") (pintype "passive"))
    )
    (net (code "85") (name "unconnected-(JP6-Pad45)") (class "Default")
      (node (ref "JP6") (pin "45") (pinfunction "45_45") (pintype "passive"))
    )
    (net (code "86") (name "unconnected-(JP6-Pad46)") (class "Default")
      (node (ref "JP6") (pin "46") (pinfunction "46_46") (pintype "passive"))
    )
    (net (code "87") (name "unconnected-(JP6-Pad47)") (class "Default")
      (node (ref "JP6") (pin "47") (pinfunction "47_47") (pintype "passive"))
    )
    (net (code "88") (name "unconnected-(JP6-Pad48)") (class "Default")
      (node (ref "JP6") (pin "48") (pinfunction "48_48") (pintype "passive"))
    )
    (net (code "89") (name "unconnected-(JP7-Pad1)") (class "Default")
      (node (ref "JP7") (pin "1") (pinfunction "1_1") (pintype "passive"))
    )
    (net (code "90") (name "unconnected-(JP7-Pad2)") (class "Default")
      (node (ref "JP7") (pin "2") (pinfunction "2_2") (pintype "passive"))
    )
    (net (code "91") (name "unconnected-(JP7-Pad3)") (class "Default")
      (node (ref "JP7") (pin "3") (pinfunction "3_3") (pintype "passive"))
    )
    (net (code "92") (name "unconnected-(JP7-Pad5)") (class "Default")
      (node (ref "JP7") (pin "5") (pinfunction "5_5") (pintype "passive"))
    )
    (net (code "93") (name "unconnected-(JP7-Pad7)") (class "Default")
      (node (ref "JP7") (pin "7") (pinfunction "7_7") (pintype "passive"))
    )
    (net (code "94") (name "unconnected-(JP7-Pad8)") (class "Default")
      (node (ref "JP7") (pin "8") (pinfunction "8_8") (pintype "passive"))
    )
    (net (code "95") (name "unconnected-(JP7-Pad9)") (class "Default")
      (node (ref "JP7") (pin "9") (pinfunction "9_9") (pintype "passive"))
    )
    (net (code "96") (name "unconnected-(JP7-Pad10)") (class "Default")
      (node (ref "JP7") (pin "10") (pinfunction "10_10") (pintype "passive"))
    )
    (net (code "97") (name "unconnected-(JP7-Pad11)") (class "Default")
      (node (ref "JP7") (pin "11") (pinfunction "11_11") (pintype "passive"))
    )
    (net (code "98") (name "unconnected-(JP7-Pad12)") (class "Default")
      (node (ref "JP7") (pin "12") (pinfunction "12_12") (pintype "passive"))
    )
    (net (code "99") (name "unconnected-(JP7-Pad13)") (class "Default")
      (node (ref "JP7") (pin "13") (pinfunction "13_13") (pintype "passive"))
    )
    (net (code "100") (name "unconnected-(JP7-Pad14)") (class "Default")
      (node (ref "JP7") (pin "14") (pinfunction "14_14") (pintype "passive"))
    )
    (net (code "101") (name "unconnected-(JP7-Pad15)") (class "Default")
      (node (ref "JP7") (pin "15") (pinfunction "15_15") (pintype "passive"))
    )
    (net (code "102") (name "unconnected-(JP7-Pad16)") (class "Default")
      (node (ref "JP7") (pin "16") (pinfunction "16_16") (pintype "passive"))
    )
    (net (code "103") (name "unconnected-(JP7-Pad17)") (class "Default")
      (node (ref "JP7") (pin "17") (pinfunction "17_17") (pintype "passive"))
    )
    (net (code "104") (name "unconnected-(JP7-Pad18)") (class "Default")
      (node (ref "JP7") (pin "18") (pinfunction "18_18") (pintype "passive"))
    )
    (net (code "105") (name "unconnected-(JP7-Pad19)") (class "Default")
      (node (ref "JP7") (pin "19") (pinfunction "19_19") (pintype "passive"))
    )
    (net (code "106") (name "unconnected-(JP7-Pad20)") (class "Default")
      (node (ref "JP7") (pin "20") (pinfunction "20_20") (pintype "passive"))
    )
    (net (code "107") (name "unconnected-(JP7-Pad21)") (class "Default")
      (node (ref "JP7") (pin "21") (pinfunction "21_21") (pintype "passive"))
    )
    (net (code "108") (name "unconnected-(JP7-Pad22)") (class "Default")
      (node (ref "JP7") (pin "22") (pinfunction "22_22") (pintype "passive"))
    )
    (net (code "109") (name "unconnected-(JP7-Pad25)") (class "Default")
      (node (ref "JP7") (pin "25") (pinfunction "25_25") (pintype "passive"))
    )
    (net (code "110") (name "unconnected-(JP7-Pad26)") (class "Default")
      (node (ref "JP7") (pin "26") (pinfunction "26_26") (pintype "passive"))
    )
    (net (code "111") (name "unconnected-(JP7-Pad27)") (class "Default")
      (node (ref "JP7") (pin "27") (pinfunction "27_27") (pintype "passive"))
    )
    (net (code "112") (name "unconnected-(JP7-Pad28)") (class "Default")
      (node (ref "JP7") (pin "28") (pinfunction "28_28") (pintype "passive"))
    )
    (net (code "113") (name "unconnected-(JP7-Pad29)") (class "Default")
      (node (ref "JP7") (pin "29") (pinfunction "29_29") (pintype "passive"))
    )
    (net (code "114") (name "unconnected-(JP7-Pad30)") (class "Default")
      (node (ref "JP7") (pin "30") (pinfunction "30_30") (pintype "passive"))
    )
    (net (code "115") (name "unconnected-(JP7-Pad31)") (class "Default")
      (node (ref "JP7") (pin "31") (pinfunction "31_31") (pintype "passive"))
    )
    (net (code "116") (name "unconnected-(JP7-Pad32)") (class "Default")
      (node (ref "JP7") (pin "32") (pinfunction "32_32") (pintype "passive"))
    )
    (net (code "117") (name "unconnected-(JP7-Pad33)") (class "Default")
      (node (ref "JP7") (pin "33") (pinfunction "33_33") (pintype "passive"))
    )
    (net (code "118") (name "unconnected-(JP7-Pad34)") (class "Default")
      (node (ref "JP7") (pin "34") (pinfunction "34_34") (pintype "passive"))
    )
    (net (code "119") (name "unconnected-(JP7-Pad35)") (class "Default")
      (node (ref "JP7") (pin "35") (pinfunction "35_35") (pintype "passive"))
    )
    (net (code "120") (name "unconnected-(JP7-Pad36)") (class "Default")
      (node (ref "JP7") (pin "36") (pinfunction "36_36") (pintype "passive"))
    )
    (net (code "121") (name "unconnected-(JP7-Pad37)") (class "Default")
      (node (ref "JP7") (pin "37") (pinfunction "37_37") (pintype "passive"))
    )
    (net (code "122") (name "unconnected-(JP7-Pad38)") (class "Default")
      (node (ref "JP7") (pin "38") (pinfunction "38_38") (pintype "passive"))
    )
    (net (code "123") (name "unconnected-(JP7-Pad39)") (class "Default")
      (node (ref "JP7") (pin "39") (pinfunction "39_39") (pintype "passive"))
    )
    (net (code "124") (name "unconnected-(JP7-Pad40)") (class "Default")
      (node (ref "JP7") (pin "40") (pinfunction "40_40") (pintype "passive"))
    )
    (net (code "125") (name "unconnected-(JP7-Pad41)") (class "Default")
      (node (ref "JP7") (pin "41") (pinfunction "41_41") (pintype "passive"))
    )
    (net (code "126") (name "unconnected-(JP7-Pad42)") (class "Default")
      (node (ref "JP7") (pin "42") (pinfunction "42_42") (pintype "passive"))
    )
    (net (code "127") (name "unconnected-(JP7-Pad43)") (class "Default")
      (node (ref "JP7") (pin "43") (pinfunction "43_43") (pintype "passive"))
    )
    (net (code "128") (name "unconnected-(JP7-Pad44)") (class "Default")
      (node (ref "JP7") (pin "44") (pinfunction "44_44") (pintype "passive"))
    )
    (net (code "129") (name "unconnected-(JP7-Pad45)") (class "Default")
      (node (ref "JP7") (pin "45") (pinfunction "45_45") (pintype "passive"))
    )
    (net (code "130") (name "unconnected-(JP7-Pad46)") (class "Default")
      (node (ref "JP7") (pin "46") (pinfunction "46_46") (pintype "passive"))
    )
    (net (code "131") (name "unconnected-(JP7-Pad48)") (class "Default")
      (node (ref "JP7") (pin "48") (pinfunction "48_48") (pintype "passive"))
    )
    (net (code "132") (name "unconnected-(POWER-Pad3)") (class "Default")
      (node (ref "POWER") (pin "3") (pinfunction "3_3") (pintype "passive"))
    )
  )
)
